# test_ckt_2.net
KiCad netlist of a schematic drawn in EAGLE
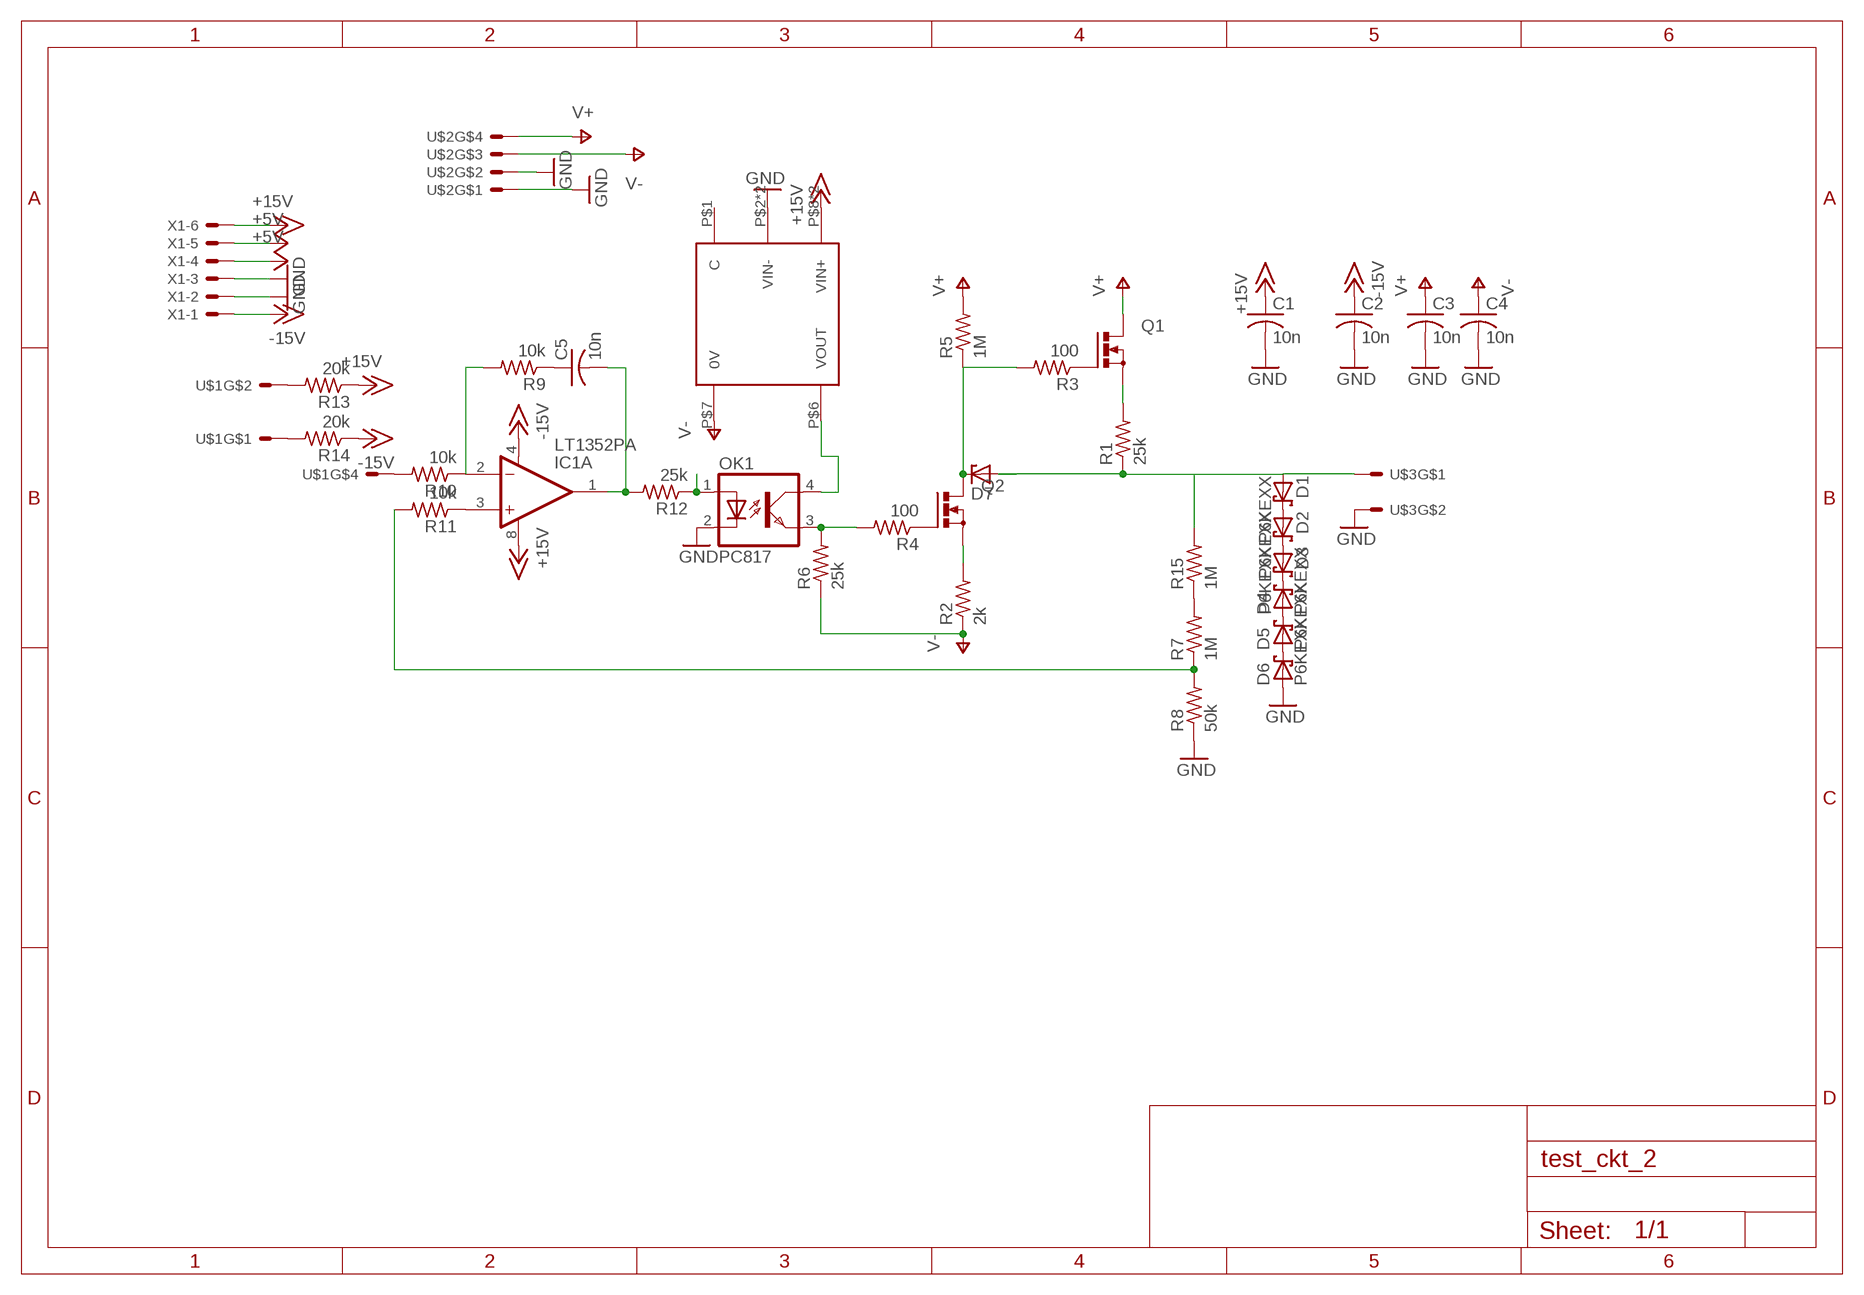
[diagram p0: schematic, sheet 1]

(export (version "E")
  (design (tool "Eeschema 10.0.6"))
  (components
    (comp (ref "C1")
      (value "10n")
      (footprint "eagle-import:C075-032X103")
      (libsource (lib "eagle-import") (part "C-US075-032X103"))
    )
    (comp (ref "C2")
      (value "10n")
      (footprint "eagle-import:C075-032X103")
      (libsource (lib "eagle-import") (part "C-US075-032X103"))
    )
    (comp (ref "C3")
      (value "10n")
      (footprint "eagle-import:C075-032X103")
      (libsource (lib "eagle-import") (part "C-US075-032X103"))
    )
    (comp (ref "C4")
      (value "10n")
      (footprint "eagle-import:C075-032X103")
      (libsource (lib "eagle-import") (part "C-US075-032X103"))
    )
    (comp (ref "C5")
      (value "10n")
      (footprint "eagle-import:C075-032X103")
      (libsource (lib "eagle-import") (part "C-US075-032X103"))
    )
    (comp (ref "D1")
      (value "P6KEXX")
      (footprint "eagle-import:CB417-15")
      (libsource (lib "eagle-import") (part "P6KEXX"))
    )
    (comp (ref "D2")
      (value "P6KEXX")
      (footprint "eagle-import:CB417-15")
      (libsource (lib "eagle-import") (part "P6KEXX"))
    )
    (comp (ref "D3")
      (value "P6KEXX")
      (footprint "eagle-import:CB417-15")
      (libsource (lib "eagle-import") (part "P6KEXX"))
    )
    (comp (ref "D4")
      (value "P6KEXX")
      (footprint "eagle-import:CB417-15")
      (libsource (lib "eagle-import") (part "P6KEXX"))
    )
    (comp (ref "D5")
      (value "P6KEXX")
      (footprint "eagle-import:CB417-15")
      (libsource (lib "eagle-import") (part "P6KEXX"))
    )
    (comp (ref "D6")
      (value "P6KEXX")
      (footprint "eagle-import:CB417-15")
      (libsource (lib "eagle-import") (part "P6KEXX"))
    )
    (comp (ref "D7")
      (value "ZENER-DIODEZD-12.5")
      (footprint "eagle-import:ZDIO12.5")
      (libsource (lib "eagle-import") (part "ZENER-DIODEZD-12.5"))
    )
    (comp (ref "DC1")
      (value "NCS")
      (footprint "eagle-import:NCS")
      (libsource (lib "eagle-import") (part "NCS"))
    )
    (comp (ref "IC1")
      (value "LT1352PA")
      (footprint "eagle-import:DIL08")
      (libsource (lib "eagle-import") (part "LT1352PA"))
    )
    (comp (ref "OK1")
      (value "PC817")
      (footprint "eagle-import:DIL04")
      (fields (field (name "MPN") "PC817X4J000F"))
      (libsource (lib "eagle-import") (part "PC817"))
    )
    (comp (ref "Q1")
      (value "PMOSFET_NTO220BV")
      (footprint "eagle-import:TO220BV")
      (libsource (lib "eagle-import") (part "PMOSFET_NTO220BV"))
    )
    (comp (ref "Q2")
      (value "PMOSFET_NTO220BV")
      (footprint "eagle-import:TO220BV")
      (libsource (lib "eagle-import") (part "PMOSFET_NTO220BV"))
    )
    (comp (ref "R1")
      (value "25k")
      (footprint "eagle-import:0207_10")
      (libsource (lib "eagle-import") (part "R-US_0207/10"))
    )
    (comp (ref "R2")
      (value "2k")
      (footprint "eagle-import:0207_10")
      (libsource (lib "eagle-import") (part "R-US_0207/10"))
    )
    (comp (ref "R3")
      (value "100")
      (footprint "eagle-import:0207_10")
      (libsource (lib "eagle-import") (part "R-US_0207/10"))
    )
    (comp (ref "R4")
      (value "100")
      (footprint "eagle-import:0207_10")
      (libsource (lib "eagle-import") (part "R-US_0207/10"))
    )
    (comp (ref "R5")
      (value "1M")
      (footprint "eagle-import:0414_15")
      (libsource (lib "eagle-import") (part "resistor_R-US_0414/15"))
    )
    (comp (ref "R6")
      (value "25k")
      (footprint "eagle-import:0207_10")
      (libsource (lib "eagle-import") (part "R-US_0207/10"))
    )
    (comp (ref "R7")
      (value "1M")
      (footprint "eagle-import:0414_15")
      (libsource (lib "eagle-import") (part "resistor_R-US_0414/15"))
    )
    (comp (ref "R8")
      (value "50k")
      (footprint "eagle-import:0207_10")
      (libsource (lib "eagle-import") (part "R-US_0207/10"))
    )
    (comp (ref "R9")
      (value "10k")
      (footprint "eagle-import:0207_10")
      (libsource (lib "eagle-import") (part "R-US_0207/10"))
    )
    (comp (ref "R10")
      (value "10k")
      (footprint "eagle-import:0207_10")
      (libsource (lib "eagle-import") (part "R-US_0207/10"))
    )
    (comp (ref "R11")
      (value "10k")
      (footprint "eagle-import:0207_10")
      (libsource (lib "eagle-import") (part "R-US_0207/10"))
    )
    (comp (ref "R12")
      (value "25k")
      (footprint "eagle-import:0207_15")
      (libsource (lib "eagle-import") (part "R-US_0207/15"))
    )
    (comp (ref "R13")
      (value "20k")
      (footprint "eagle-import:0207_10")
      (libsource (lib "eagle-import") (part "R-US_0207/10"))
    )
    (comp (ref "R14")
      (value "20k")
      (footprint "eagle-import:0207_10")
      (libsource (lib "eagle-import") (part "R-US_0207/10"))
    )
    (comp (ref "R15")
      (value "1M")
      (footprint "eagle-import:0414_15")
      (libsource (lib "eagle-import") (part "resistor_R-US_0414/15"))
    )
    (comp (ref "U$1")
      (value "5569-4")
      (footprint "eagle-import:5669-4")
      (libsource (lib "eagle-import") (part "5569-4"))
    )
    (comp (ref "U$2")
      (value "5569-4")
      (footprint "eagle-import:5669-4")
      (libsource (lib "eagle-import") (part "5569-4"))
    )
    (comp (ref "U$3")
      (value "5569-2")
      (footprint "eagle-import:5569-2")
      (libsource (lib "eagle-import") (part "5569-2"))
    )
    (comp (ref "X1")
      (value "KK-156-6")
      (footprint "eagle-import:KK-156-6")
      (libsource (lib "eagle-import") (part "KK-156-6"))
    )
  )
  (nets
    (net (code "1") (name "+5V") (class "Default")
      (node (ref "X1") (pin "4") (pinfunction "S_4") (pintype "passive"))
      (node (ref "X1") (pin "5") (pinfunction "S_5") (pintype "passive"))
    )
    (net (code "2") (name "+15V") (class "Default")
      (node (ref "C1") (pin "1") (pinfunction "1_1") (pintype "passive"))
      (node (ref "DC1") (pin "P$8") (pinfunction "VIN+_P$8") (pintype "bidirectional"))
      (node (ref "DC1") (pin "P$9") (pinfunction "VIN+_P$9") (pintype "bidirectional"))
      (node (ref "IC1") (pin "8") (pinfunction "V+_8") (pintype "power_in"))
      (node (ref "R13") (pin "1") (pinfunction "1_1") (pintype "passive"))
      (node (ref "X1") (pin "6") (pinfunction "S_6") (pintype "passive"))
    )
    (net (code "3") (name "-15V") (class "Default")
      (node (ref "C2") (pin "1") (pinfunction "1_1") (pintype "passive"))
      (node (ref "IC1") (pin "4") (pinfunction "V-_4") (pintype "power_in"))
      (node (ref "R14") (pin "1") (pinfunction "1_1") (pintype "passive"))
      (node (ref "X1") (pin "1") (pinfunction "S_1") (pintype "passive"))
    )
    (net (code "4") (name "GND") (class "Default")
      (node (ref "C1") (pin "2") (pinfunction "2_2") (pintype "passive"))
      (node (ref "C2") (pin "2") (pinfunction "2_2") (pintype "passive"))
      (node (ref "C3") (pin "2") (pinfunction "2_2") (pintype "passive"))
      (node (ref "C4") (pin "2") (pinfunction "2_2") (pintype "passive"))
      (node (ref "D6") (pin "A") (pinfunction "A_A") (pintype "passive"))
      (node (ref "DC1") (pin "P$2") (pinfunction "VIN-_P$2") (pintype "bidirectional"))
      (node (ref "DC1") (pin "P$3") (pinfunction "VIN-_P$3") (pintype "bidirectional"))
      (node (ref "OK1") (pin "2") (pinfunction "C_2") (pintype "passive"))
      (node (ref "R8") (pin "1") (pinfunction "1_1") (pintype "passive"))
      (node (ref "U$2") (pin "P$1") (pinfunction "S_P$1") (pintype "passive"))
      (node (ref "U$2") (pin "P$2") (pinfunction "S_P$2") (pintype "passive"))
      (node (ref "U$3") (pin "P$2") (pinfunction "S_P$2") (pintype "passive"))
      (node (ref "X1") (pin "2") (pinfunction "S_2") (pintype "passive"))
      (node (ref "X1") (pin "3") (pinfunction "S_3") (pintype "passive"))
    )
    (net (code "5") (name "Net-(C5-Pad1)") (class "Default")
      (node (ref "C5") (pin "1") (pinfunction "1_1") (pintype "passive"))
      (node (ref "R9") (pin "1") (pinfunction "1_1") (pintype "passive"))
    )
    (net (code "6") (name "Net-(D1-PadC)") (class "Default")
      (node (ref "D1") (pin "C") (pinfunction "C_C") (pintype "passive"))
      (node (ref "D2") (pin "A") (pinfunction "A_A") (pintype "passive"))
    )
    (net (code "7") (name "Net-(D2-PadC)") (class "Default")
      (node (ref "D2") (pin "C") (pinfunction "C_C") (pintype "passive"))
      (node (ref "D3") (pin "A") (pinfunction "A_A") (pintype "passive"))
    )
    (net (code "8") (name "Net-(D3-PadC)") (class "Default")
      (node (ref "D3") (pin "C") (pinfunction "C_C") (pintype "passive"))
      (node (ref "D4") (pin "C") (pinfunction "C_C") (pintype "passive"))
    )
    (net (code "9") (name "Net-(D4-PadA)") (class "Default")
      (node (ref "D4") (pin "A") (pinfunction "A_A") (pintype "passive"))
      (node (ref "D5") (pin "C") (pinfunction "C_C") (pintype "passive"))
    )
    (net (code "10") (name "Net-(D5-PadA)") (class "Default")
      (node (ref "D5") (pin "A") (pinfunction "A_A") (pintype "passive"))
      (node (ref "D6") (pin "C") (pinfunction "C_C") (pintype "passive"))
    )
    (net (code "11") (name "Net-(D7-PadC)") (class "Default")
      (node (ref "D7") (pin "C") (pinfunction "C_C") (pintype "passive"))
      (node (ref "Q2") (pin "D") (pinfunction "D_D") (pintype "passive"))
      (node (ref "R3") (pin "2") (pinfunction "2_2") (pintype "passive"))
      (node (ref "R5") (pin "1") (pinfunction "1_1") (pintype "passive"))
    )
    (net (code "12") (name "Net-(DC1-VOUT)") (class "Default")
      (node (ref "DC1") (pin "P$6") (pinfunction "VOUT_P$6") (pintype "bidirectional"))
      (node (ref "OK1") (pin "4") (pinfunction "COL_4") (pintype "passive"))
    )
    (net (code "13") (name "Net-(IC1A-+IN)") (class "Default")
      (node (ref "IC1") (pin "3") (pinfunction "+IN_3") (pintype "input"))
      (node (ref "R11") (pin "1") (pinfunction "1_1") (pintype "passive"))
    )
    (net (code "14") (name "Net-(IC1A--IN)") (class "Default")
      (node (ref "IC1") (pin "2") (pinfunction "-IN_2") (pintype "input"))
      (node (ref "R10") (pin "1") (pinfunction "1_1") (pintype "passive"))
      (node (ref "R9") (pin "2") (pinfunction "2_2") (pintype "passive"))
    )
    (net (code "15") (name "Net-(IC1A-OUT)") (class "Default")
      (node (ref "C5") (pin "2") (pinfunction "2_2") (pintype "passive"))
      (node (ref "IC1") (pin "1") (pinfunction "OUT_1") (pintype "output"))
      (node (ref "R12") (pin "2") (pinfunction "2_2") (pintype "passive"))
    )
    (net (code "16") (name "Net-(OK1-A)") (class "Default")
      (node (ref "OK1") (pin "1") (pinfunction "A_1") (pintype "passive"))
      (node (ref "R12") (pin "1") (pinfunction "1_1") (pintype "passive"))
    )
    (net (code "17") (name "Net-(OK1-EMIT)") (class "Default")
      (node (ref "OK1") (pin "3") (pinfunction "EMIT_3") (pintype "passive"))
      (node (ref "R4") (pin "2") (pinfunction "2_2") (pintype "passive"))
      (node (ref "R6") (pin "2") (pinfunction "2_2") (pintype "passive"))
    )
    (net (code "18") (name "Net-(Q1-PadG)") (class "Default")
      (node (ref "Q1") (pin "G") (pinfunction "G_G") (pintype "passive"))
      (node (ref "R3") (pin "1") (pinfunction "1_1") (pintype "passive"))
    )
    (net (code "19") (name "Net-(Q1-PadS)") (class "Default")
      (node (ref "Q1") (pin "S") (pinfunction "S_S") (pintype "passive"))
      (node (ref "R1") (pin "2") (pinfunction "2_2") (pintype "passive"))
    )
    (net (code "20") (name "Net-(Q2-PadG)") (class "Default")
      (node (ref "Q2") (pin "G") (pinfunction "G_G") (pintype "passive"))
      (node (ref "R4") (pin "1") (pinfunction "1_1") (pintype "passive"))
    )
    (net (code "21") (name "Net-(Q2-PadS)") (class "Default")
      (node (ref "Q2") (pin "S") (pinfunction "S_S") (pintype "passive"))
      (node (ref "R2") (pin "2") (pinfunction "2_2") (pintype "passive"))
    )
    (net (code "22") (name "Net-(R11-Pad2)") (class "Default")
      (node (ref "R11") (pin "2") (pinfunction "2_2") (pintype "passive"))
      (node (ref "R7") (pin "1") (pinfunction "1_1") (pintype "passive"))
      (node (ref "R8") (pin "2") (pinfunction "2_2") (pintype "passive"))
    )
    (net (code "23") (name "Net-(R15-Pad1)") (class "Default")
      (node (ref "R15") (pin "1") (pinfunction "1_1") (pintype "passive"))
      (node (ref "R7") (pin "2") (pinfunction "2_2") (pintype "passive"))
    )
    (net (code "24") (name "Net-(U$1A-S)") (class "Default")
      (node (ref "R14") (pin "2") (pinfunction "2_2") (pintype "passive"))
      (node (ref "U$1") (pin "P$1") (pinfunction "S_P$1") (pintype "passive"))
    )
    (net (code "25") (name "Net-(U$1B-S)") (class "Default")
      (node (ref "R13") (pin "2") (pinfunction "2_2") (pintype "passive"))
      (node (ref "U$1") (pin "P$2") (pinfunction "S_P$2") (pintype "passive"))
    )
    (net (code "26") (name "Net-(U$1D-S)") (class "Default")
      (node (ref "R10") (pin "2") (pinfunction "2_2") (pintype "passive"))
      (node (ref "U$1") (pin "P$4") (pinfunction "S_P$4") (pintype "passive"))
    )
    (net (code "27") (name "Net-(U$3A-S)") (class "Default")
      (node (ref "D1") (pin "A") (pinfunction "A_A") (pintype "passive"))
      (node (ref "D7") (pin "A") (pinfunction "A_A") (pintype "passive"))
      (node (ref "R1") (pin "1") (pinfunction "1_1") (pintype "passive"))
      (node (ref "R15") (pin "2") (pinfunction "2_2") (pintype "passive"))
      (node (ref "U$3") (pin "P$1") (pinfunction "S_P$1") (pintype "passive"))
    )
    (net (code "28") (name "V+") (class "Default")
      (node (ref "C3") (pin "1") (pinfunction "1_1") (pintype "passive"))
      (node (ref "Q1") (pin "D") (pinfunction "D_D") (pintype "passive"))
      (node (ref "R5") (pin "2") (pinfunction "2_2") (pintype "passive"))
      (node (ref "U$2") (pin "P$4") (pinfunction "S_P$4") (pintype "passive"))
    )
    (net (code "29") (name "V-") (class "Default")
      (node (ref "C4") (pin "1") (pinfunction "1_1") (pintype "passive"))
      (node (ref "DC1") (pin "P$7") (pinfunction "0V_P$7") (pintype "bidirectional"))
      (node (ref "R2") (pin "1") (pinfunction "1_1") (pintype "passive"))
      (node (ref "R6") (pin "1") (pinfunction "1_1") (pintype "passive"))
      (node (ref "U$2") (pin "P$3") (pinfunction "S_P$3") (pintype "passive"))
    )
    (net (code "30") (name "unconnected-(DC1-C-PadP$1)") (class "Default")
      (node (ref "DC1") (pin "P$1") (pinfunction "C_P$1") (pintype "bidirectional"))
    )
  )
)
